# TelemetryBridge.net
KiCad netlist of a schematic drawn in EAGLE
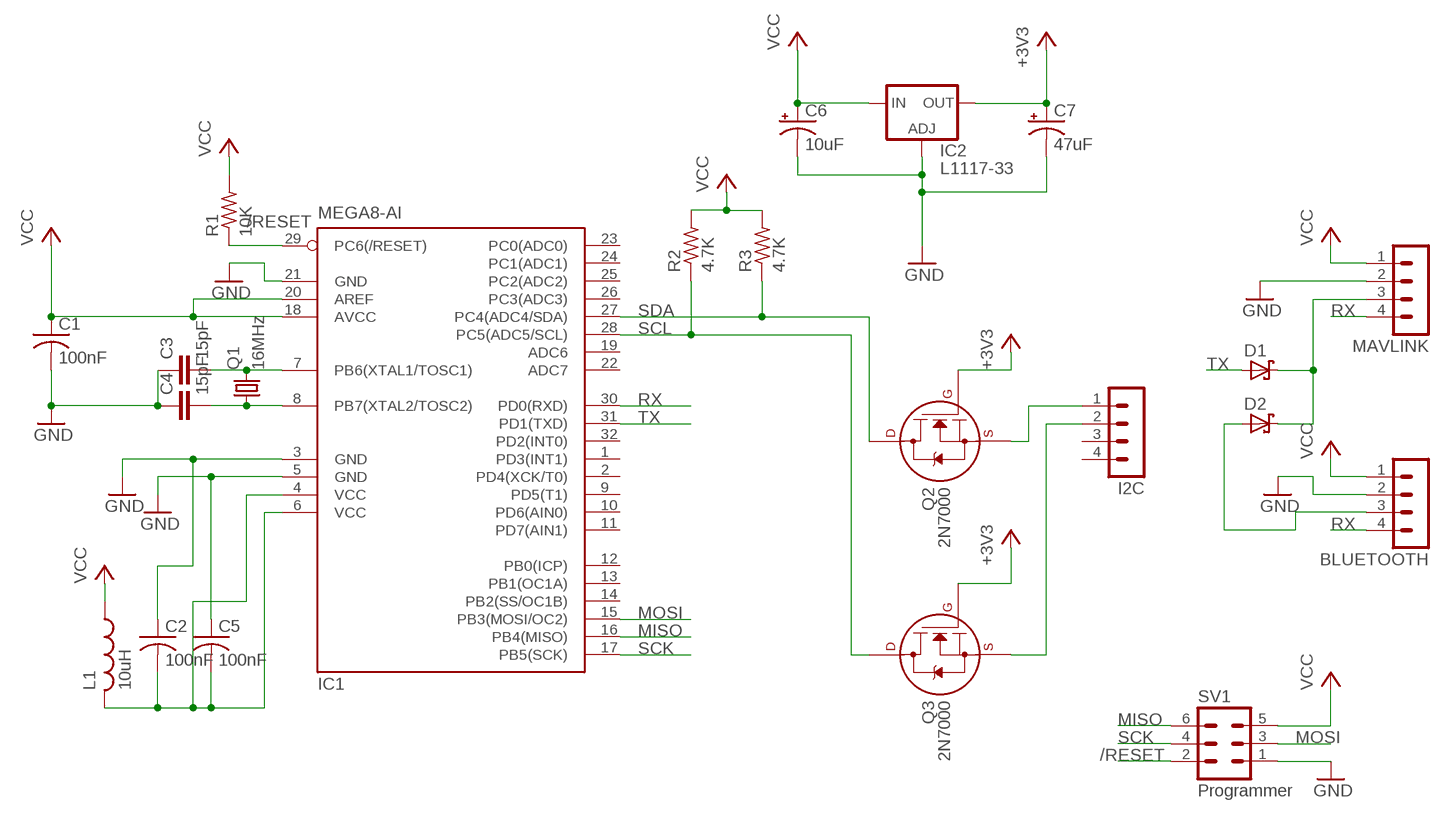
[diagram p0: schematic, sheet 1]

(export (version "E")
  (design (tool "Eeschema 10.0.6"))
  (components
    (comp (ref "BLUETOOTH")
      (value "MA04-1")
      (footprint "eagle-import:MA04-1")
      (libsource (lib "eagle-import") (part "MA04-1"))
    )
    (comp (ref "C1")
      (value "100nF")
      (footprint "eagle-import:C0805")
      (libsource (lib "eagle-import") (part "C-USC0805"))
    )
    (comp (ref "C2")
      (value "100nF")
      (footprint "eagle-import:C0805")
      (libsource (lib "eagle-import") (part "C-USC0805"))
    )
    (comp (ref "C3")
      (value "15pF")
      (footprint "eagle-import:C0805")
      (libsource (lib "eagle-import") (part "C-EUC0805"))
    )
    (comp (ref "C4")
      (value "15pF")
      (footprint "eagle-import:C0805")
      (libsource (lib "eagle-import") (part "C-EUC0805"))
    )
    (comp (ref "C5")
      (value "100nF")
      (footprint "eagle-import:C0805")
      (libsource (lib "eagle-import") (part "C-USC0805"))
    )
    (comp (ref "C6")
      (value "10uF")
      (footprint "eagle-import:PANASONIC_C")
      (libsource (lib "eagle-import") (part "CPOL-USC"))
    )
    (comp (ref "C7")
      (value "47uF")
      (footprint "eagle-import:PANASONIC_D")
      (libsource (lib "eagle-import") (part "CPOL-USD"))
    )
    (comp (ref "D1")
      (value "SCHOTTKY-DIODE")
      (footprint "eagle-import:DO-214AC")
      (libsource (lib "eagle-import") (part "SCHOTTKY-DIODE"))
    )
    (comp (ref "D2")
      (value "SCHOTTKY-DIODE")
      (footprint "eagle-import:DO-214AC")
      (libsource (lib "eagle-import") (part "SCHOTTKY-DIODE"))
    )
    (comp (ref "I2C")
      (value "MA04-1")
      (footprint "eagle-import:MA04-1")
      (libsource (lib "eagle-import") (part "MA04-1"))
    )
    (comp (ref "IC1")
      (value "MEGA8-AI")
      (footprint "eagle-import:TQFP32-08")
      (fields
        (field (name "MPN") "ATMEGA8-16AU")
        (field (name "MPN_1") "ATMEGA8-16AU")
        (field (name "OC_FARNELL") "9171371")
        (field (name "OC_NEWARK") "73M8863")
      )
      (libsource (lib "eagle-import") (part "MEGA8-AI"))
    )
    (comp (ref "IC2")
      (value "L1117-33")
      (footprint "eagle-import:DPACK")
      (libsource (lib "eagle-import") (part "LD117A?DT-TR"))
    )
    (comp (ref "L1")
      (value "10uH")
      (footprint "eagle-import:0805")
      (libsource (lib "eagle-import") (part "INDUCTOR"))
    )
    (comp (ref "MAVLINK")
      (value "MA04-1")
      (footprint "eagle-import:MA04-1")
      (libsource (lib "eagle-import") (part "MA04-1"))
    )
    (comp (ref "Q1")
      (value "16MHz")
      (footprint "eagle-import:CSM-7X-DU")
      (libsource (lib "eagle-import") (part "CSM-7X-DU"))
    )
    (comp (ref "Q2")
      (value "2N7000")
      (footprint "eagle-import:SOT-23")
      (libsource (lib "eagle-import") (part "2N700_SOT232A"))
    )
    (comp (ref "Q3")
      (value "2N7000")
      (footprint "eagle-import:SOT-23")
      (libsource (lib "eagle-import") (part "2N700_SOT232A"))
    )
    (comp (ref "R1")
      (value "10K")
      (footprint "eagle-import:R0805")
      (libsource (lib "eagle-import") (part "R-US_R0805"))
    )
    (comp (ref "R2")
      (value "4.7K")
      (footprint "eagle-import:R0805")
      (libsource (lib "eagle-import") (part "R-US_R0805"))
    )
    (comp (ref "R3")
      (value "4.7K")
      (footprint "eagle-import:R0805")
      (libsource (lib "eagle-import") (part "R-US_R0805"))
    )
    (comp (ref "SV1")
      (value "Programmer")
      (footprint "eagle-import:KEVINSLIB_MA03-2")
      (libsource (lib "eagle-import") (part "KEVINSLIB_MA03-2"))
    )
  )
  (nets
    (net (code "1") (name "+3V3") (class "Default")
      (node (ref "C7") (pin "+") (pinfunction "+_+") (pintype "passive"))
      (node (ref "IC2") (pin "4") (pinfunction "OUT_4") (pintype "passive"))
      (node (ref "Q2") (pin "1") (pinfunction "G_1") (pintype "tri_state"))
      (node (ref "Q3") (pin "1") (pinfunction "G_1") (pintype "tri_state"))
    )
    (net (code "2") (name "/MISO") (class "Default")
      (node (ref "IC1") (pin "16") (pinfunction "PB4(MISO)_16") (pintype "bidirectional"))
      (node (ref "SV1") (pin "6") (pinfunction "6_6") (pintype "passive"))
    )
    (net (code "3") (name "/MOSI") (class "Default")
      (node (ref "IC1") (pin "15") (pinfunction "PB3(MOSI/OC2)_15") (pintype "bidirectional"))
      (node (ref "SV1") (pin "3") (pinfunction "3_3") (pintype "passive"))
    )
    (net (code "4") (name "/RX") (class "Default")
      (node (ref "BLUETOOTH") (pin "4") (pinfunction "4_4") (pintype "passive"))
      (node (ref "IC1") (pin "30") (pinfunction "PD0(RXD)_30") (pintype "bidirectional"))
      (node (ref "MAVLINK") (pin "4") (pinfunction "4_4") (pintype "passive"))
    )
    (net (code "5") (name "/SCK") (class "Default")
      (node (ref "IC1") (pin "17") (pinfunction "PB5(SCK)_17") (pintype "bidirectional"))
      (node (ref "SV1") (pin "4") (pinfunction "4_4") (pintype "passive"))
    )
    (net (code "6") (name "/SCL") (class "Default")
      (node (ref "IC1") (pin "28") (pinfunction "PC5(ADC5/SCL)_28") (pintype "bidirectional"))
      (node (ref "Q3") (pin "3") (pinfunction "D_3") (pintype "bidirectional"))
      (node (ref "R2") (pin "1") (pinfunction "1_1") (pintype "passive"))
    )
    (net (code "7") (name "/SDA") (class "Default")
      (node (ref "IC1") (pin "27") (pinfunction "PC4(ADC4/SDA)_27") (pintype "bidirectional"))
      (node (ref "Q2") (pin "3") (pinfunction "D_3") (pintype "bidirectional"))
      (node (ref "R3") (pin "1") (pinfunction "1_1") (pintype "passive"))
    )
    (net (code "8") (name "/TX") (class "Default")
      (node (ref "D1") (pin "A") (pinfunction "A_A") (pintype "passive"))
      (node (ref "IC1") (pin "31") (pinfunction "PD1(TXD)_31") (pintype "bidirectional"))
    )
    (net (code "9") (name "/{slash}RESET") (class "Default")
      (node (ref "IC1") (pin "29") (pinfunction "PC6(/RESET)_29") (pintype "bidirectional"))
      (node (ref "R1") (pin "1") (pinfunction "1_1") (pintype "passive"))
      (node (ref "SV1") (pin "2") (pinfunction "2_2") (pintype "passive"))
    )
    (net (code "10") (name "GND") (class "Default")
      (node (ref "BLUETOOTH") (pin "2") (pinfunction "2_2") (pintype "passive"))
      (node (ref "C1") (pin "2") (pinfunction "2_2") (pintype "passive"))
      (node (ref "C2") (pin "1") (pinfunction "1_1") (pintype "passive"))
      (node (ref "C3") (pin "1") (pinfunction "1_1") (pintype "passive"))
      (node (ref "C4") (pin "1") (pinfunction "1_1") (pintype "passive"))
      (node (ref "C5") (pin "1") (pinfunction "1_1") (pintype "passive"))
      (node (ref "C6") (pin "-") (pinfunction "-_-") (pintype "passive"))
      (node (ref "C7") (pin "-") (pinfunction "-_-") (pintype "passive"))
      (node (ref "IC1") (pin "21") (pinfunction "GND_21") (pintype "power_in"))
      (node (ref "IC1") (pin "3") (pinfunction "GND_3") (pintype "power_in"))
      (node (ref "IC1") (pin "5") (pinfunction "GND_5") (pintype "power_in"))
      (node (ref "IC2") (pin "1") (pinfunction "ADJ_1") (pintype "input"))
      (node (ref "MAVLINK") (pin "2") (pinfunction "2_2") (pintype "passive"))
      (node (ref "SV1") (pin "1") (pinfunction "1_1") (pintype "passive"))
    )
    (net (code "11") (name "Net-(BLUETOOTH-Pad3)") (class "Default")
      (node (ref "BLUETOOTH") (pin "3") (pinfunction "3_3") (pintype "passive"))
      (node (ref "D2") (pin "A") (pinfunction "A_A") (pintype "passive"))
    )
    (net (code "12") (name "Net-(C2-Pad2)") (class "Default")
      (node (ref "C2") (pin "2") (pinfunction "2_2") (pintype "passive"))
      (node (ref "C5") (pin "2") (pinfunction "2_2") (pintype "passive"))
      (node (ref "IC1") (pin "4") (pinfunction "VCC_4") (pintype "power_in"))
      (node (ref "IC1") (pin "6") (pinfunction "VCC_6") (pintype "power_in"))
      (node (ref "L1") (pin "2") (pinfunction "2_2") (pintype "passive"))
    )
    (net (code "13") (name "Net-(D1-PadC)") (class "Default")
      (node (ref "D1") (pin "C") (pinfunction "C_C") (pintype "passive"))
      (node (ref "D2") (pin "C") (pinfunction "C_C") (pintype "passive"))
      (node (ref "MAVLINK") (pin "3") (pinfunction "3_3") (pintype "passive"))
    )
    (net (code "14") (name "Net-(IC1-PB6(XTAL1{slash}TOSC1))") (class "Default")
      (node (ref "C3") (pin "2") (pinfunction "2_2") (pintype "passive"))
      (node (ref "IC1") (pin "7") (pinfunction "PB6(XTAL1/TOSC1)_7") (pintype "bidirectional"))
      (node (ref "Q1") (pin "2") (pinfunction "2_2") (pintype "passive"))
    )
    (net (code "15") (name "Net-(IC1-PB7(XTAL2{slash}TOSC2))") (class "Default")
      (node (ref "C4") (pin "2") (pinfunction "2_2") (pintype "passive"))
      (node (ref "IC1") (pin "8") (pinfunction "PB7(XTAL2/TOSC2)_8") (pintype "bidirectional"))
      (node (ref "Q1") (pin "1") (pinfunction "1_1") (pintype "passive"))
    )
    (net (code "16") (name "Net-(Q2-S)") (class "Default")
      (node (ref "I2C") (pin "1") (pinfunction "1_1") (pintype "passive"))
      (node (ref "Q2") (pin "2") (pinfunction "S_2") (pintype "bidirectional"))
    )
    (net (code "17") (name "Net-(Q3-S)") (class "Default")
      (node (ref "I2C") (pin "2") (pinfunction "2_2") (pintype "passive"))
      (node (ref "Q3") (pin "2") (pinfunction "S_2") (pintype "bidirectional"))
    )
    (net (code "18") (name "VCC") (class "Default")
      (node (ref "BLUETOOTH") (pin "1") (pinfunction "1_1") (pintype "passive"))
      (node (ref "C1") (pin "1") (pinfunction "1_1") (pintype "passive"))
      (node (ref "C6") (pin "+") (pinfunction "+_+") (pintype "passive"))
      (node (ref "IC1") (pin "18") (pinfunction "AVCC_18") (pintype "power_in"))
      (node (ref "IC1") (pin "20") (pinfunction "AREF_20") (pintype "passive"))
      (node (ref "IC2") (pin "3") (pinfunction "IN_3") (pintype "input"))
      (node (ref "L1") (pin "1") (pinfunction "1_1") (pintype "passive"))
      (node (ref "MAVLINK") (pin "1") (pinfunction "1_1") (pintype "passive"))
      (node (ref "R1") (pin "2") (pinfunction "2_2") (pintype "passive"))
      (node (ref "R2") (pin "2") (pinfunction "2_2") (pintype "passive"))
      (node (ref "R3") (pin "2") (pinfunction "2_2") (pintype "passive"))
      (node (ref "SV1") (pin "5") (pinfunction "5_5") (pintype "passive"))
    )
    (net (code "19") (name "unconnected-(I2C-Pad3)") (class "Default")
      (node (ref "I2C") (pin "3") (pinfunction "3_3") (pintype "passive"))
    )
    (net (code "20") (name "unconnected-(I2C-Pad4)") (class "Default")
      (node (ref "I2C") (pin "4") (pinfunction "4_4") (pintype "passive"))
    )
    (net (code "21") (name "unconnected-(IC1-ADC6-Pad19)") (class "Default")
      (node (ref "IC1") (pin "19") (pinfunction "ADC6_19") (pintype "bidirectional"))
    )
    (net (code "22") (name "unconnected-(IC1-ADC7-Pad22)") (class "Default")
      (node (ref "IC1") (pin "22") (pinfunction "ADC7_22") (pintype "bidirectional"))
    )
    (net (code "23") (name "unconnected-(IC1-PB0(ICP)-Pad12)") (class "Default")
      (node (ref "IC1") (pin "12") (pinfunction "PB0(ICP)_12") (pintype "bidirectional"))
    )
    (net (code "24") (name "unconnected-(IC1-PB1(OC1A)-Pad13)") (class "Default")
      (node (ref "IC1") (pin "13") (pinfunction "PB1(OC1A)_13") (pintype "bidirectional"))
    )
    (net (code "25") (name "unconnected-(IC1-PB2(SS{slash}OC1B)-Pad14)") (class "Default")
      (node (ref "IC1") (pin "14") (pinfunction "PB2(SS/OC1B)_14") (pintype "bidirectional"))
    )
    (net (code "26") (name "unconnected-(IC1-PC0(ADC0)-Pad23)") (class "Default")
      (node (ref "IC1") (pin "23") (pinfunction "PC0(ADC0)_23") (pintype "bidirectional"))
    )
    (net (code "27") (name "unconnected-(IC1-PC1(ADC1)-Pad24)") (class "Default")
      (node (ref "IC1") (pin "24") (pinfunction "PC1(ADC1)_24") (pintype "bidirectional"))
    )
    (net (code "28") (name "unconnected-(IC1-PC2(ADC2)-Pad25)") (class "Default")
      (node (ref "IC1") (pin "25") (pinfunction "PC2(ADC2)_25") (pintype "bidirectional"))
    )
    (net (code "29") (name "unconnected-(IC1-PC3(ADC3)-Pad26)") (class "Default")
      (node (ref "IC1") (pin "26") (pinfunction "PC3(ADC3)_26") (pintype "bidirectional"))
    )
    (net (code "30") (name "unconnected-(IC1-PD2(INT0)-Pad32)") (class "Default")
      (node (ref "IC1") (pin "32") (pinfunction "PD2(INT0)_32") (pintype "bidirectional"))
    )
    (net (code "31") (name "unconnected-(IC1-PD3(INT1)-Pad1)") (class "Default")
      (node (ref "IC1") (pin "1") (pinfunction "PD3(INT1)_1") (pintype "bidirectional"))
    )
    (net (code "32") (name "unconnected-(IC1-PD4(XCK{slash}T0)-Pad2)") (class "Default")
      (node (ref "IC1") (pin "2") (pinfunction "PD4(XCK/T0)_2") (pintype "bidirectional"))
    )
    (net (code "33") (name "unconnected-(IC1-PD5(T1)-Pad9)") (class "Default")
      (node (ref "IC1") (pin "9") (pinfunction "PD5(T1)_9") (pintype "bidirectional"))
    )
    (net (code "34") (name "unconnected-(IC1-PD6(AIN0)-Pad10)") (class "Default")
      (node (ref "IC1") (pin "10") (pinfunction "PD6(AIN0)_10") (pintype "bidirectional"))
    )
    (net (code "35") (name "unconnected-(IC1-PD7(AIN1)-Pad11)") (class "Default")
      (node (ref "IC1") (pin "11") (pinfunction "PD7(AIN1)_11") (pintype "bidirectional"))
    )
  )
)
